# STLINK-SWD.net
KiCad netlist of a schematic drawn in Altium Designer
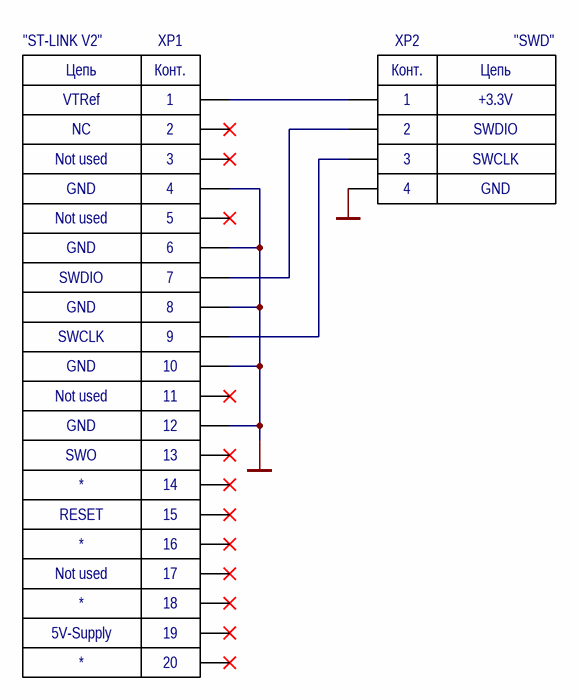
[diagram p0: STLINK-SWD.SchDoc]

(export (version "E")
  (design (tool "Eeschema 10.0.6"))
  (components
    (comp (ref "XP1")
      (value "IDC-20MR")
      (footprint "IDC-20MR")
      (description "Box Header R/A type Pitch 2.54mm")
      (fields
        (field (name "LABEL") "\"ST-LINK V2\"")
        (field (name "CIRCUIT7") "SWDIO")
        (field (name "CIRCUIT8") "GND")
        (field (name "CIRCUIT9") "SWCLK")
        (field (name "CIRCUIT10") "GND")
        (field (name "CIRCUIT11") "Not used")
        (field (name "CIRCUIT12") "GND")
        (field (name "CIRCUIT13") "SWO")
        (field (name "CIRCUIT14") "*")
        (field (name "CIRCUIT15") "RESET")
        (field (name "CIRCUIT16") "*")
        (field (name "CIRCUIT17") "Not used")
        (field (name "CIRCUIT18") "*")
        (field (name "CIRCUIT19") "5V-Supply")
        (field (name "CIRCUIT20") "*")
        (field (name "CIRCUIT6") "GND")
        (field (name "CIRCUIT4") "GND")
        (field (name "CIRCUIT5") "Not used")
        (field (name "CIRCUIT3") "Not used")
        (field (name "CIRCUIT2") "NC")
        (field (name "CIRCUIT1") "VTRef")
      )
      (libsource (lib "Connectors") (part "IDC-20MR"))
    )
    (comp (ref "XP2")
      (value "PLS-4R")
      (footprint "PLS-4R-left")
      (description "Pin Header R/A type Pitch 2.54mm")
      (fields
        (field (name "CIRCUIT4") "GND")
        (field (name "CIRCUIT3") "SWCLK")
        (field (name "CIRCUIT1") "+3.3V")
        (field (name "CIRCUIT2") "SWDIO")
        (field (name "LABEL") "\"SWD\"")
      )
      (libsource (lib "Connectors") (part "PLS-4R"))
    )
  )
  (nets
    (net (code "1") (name "GND") (class "Default")
      (node (ref "XP1") (pin "10") (pinfunction "10_10") (pintype "passive"))
      (node (ref "XP1") (pin "12") (pinfunction "12_12") (pintype "passive"))
      (node (ref "XP1") (pin "4") (pinfunction "4_4") (pintype "passive"))
      (node (ref "XP1") (pin "6") (pinfunction "6_6") (pintype "passive"))
      (node (ref "XP1") (pin "8") (pinfunction "8_8") (pintype "passive"))
      (node (ref "XP2") (pin "4") (pinfunction "4_4") (pintype "passive"))
    )
    (net (code "2") (name "Net-(XP1-Pad1)") (class "Default")
      (node (ref "XP1") (pin "1") (pinfunction "1_1") (pintype "passive"))
      (node (ref "XP2") (pin "1") (pinfunction "1_1") (pintype "passive"))
    )
    (net (code "3") (name "Net-(XP1-Pad7)") (class "Default")
      (node (ref "XP1") (pin "7") (pinfunction "7_7") (pintype "passive"))
      (node (ref "XP2") (pin "2") (pinfunction "2_2") (pintype "passive"))
    )
    (net (code "4") (name "Net-(XP1-Pad9)") (class "Default")
      (node (ref "XP1") (pin "9") (pinfunction "9_9") (pintype "passive"))
      (node (ref "XP2") (pin "3") (pinfunction "3_3") (pintype "passive"))
    )
    (net (code "5") (name "unconnected-(XP1-Pad2)") (class "Default")
      (node (ref "XP1") (pin "2") (pinfunction "2_2") (pintype "passive+no_connect"))
    )
    (net (code "6") (name "unconnected-(XP1-Pad3)") (class "Default")
      (node (ref "XP1") (pin "3") (pinfunction "3_3") (pintype "passive+no_connect"))
    )
    (net (code "7") (name "unconnected-(XP1-Pad5)") (class "Default")
      (node (ref "XP1") (pin "5") (pinfunction "5_5") (pintype "passive+no_connect"))
    )
    (net (code "8") (name "unconnected-(XP1-Pad11)") (class "Default")
      (node (ref "XP1") (pin "11") (pinfunction "11_11") (pintype "passive+no_connect"))
    )
    (net (code "9") (name "unconnected-(XP1-Pad13)") (class "Default")
      (node (ref "XP1") (pin "13") (pinfunction "13_13") (pintype "passive+no_connect"))
    )
    (net (code "10") (name "unconnected-(XP1-Pad14)") (class "Default")
      (node (ref "XP1") (pin "14") (pinfunction "14_14") (pintype "passive+no_connect"))
    )
    (net (code "11") (name "unconnected-(XP1-Pad15)") (class "Default")
      (node (ref "XP1") (pin "15") (pinfunction "15_15") (pintype "passive+no_connect"))
    )
    (net (code "12") (name "unconnected-(XP1-Pad16)") (class "Default")
      (node (ref "XP1") (pin "16") (pinfunction "16_16") (pintype "passive+no_connect"))
    )
    (net (code "13") (name "unconnected-(XP1-Pad17)") (class "Default")
      (node (ref "XP1") (pin "17") (pinfunction "17_17") (pintype "passive+no_connect"))
    )
    (net (code "14") (name "unconnected-(XP1-Pad18)") (class "Default")
      (node (ref "XP1") (pin "18") (pinfunction "18_18") (pintype "passive+no_connect"))
    )
    (net (code "15") (name "unconnected-(XP1-Pad19)") (class "Default")
      (node (ref "XP1") (pin "19") (pinfunction "19_19") (pintype "passive+no_connect"))
    )
    (net (code "16") (name "unconnected-(XP1-Pad20)") (class "Default")
      (node (ref "XP1") (pin "20") (pinfunction "20_20") (pintype "passive+no_connect"))
    )
  )
)
